# v2_0.net
KiCad netlist of a schematic drawn in Altium Designer
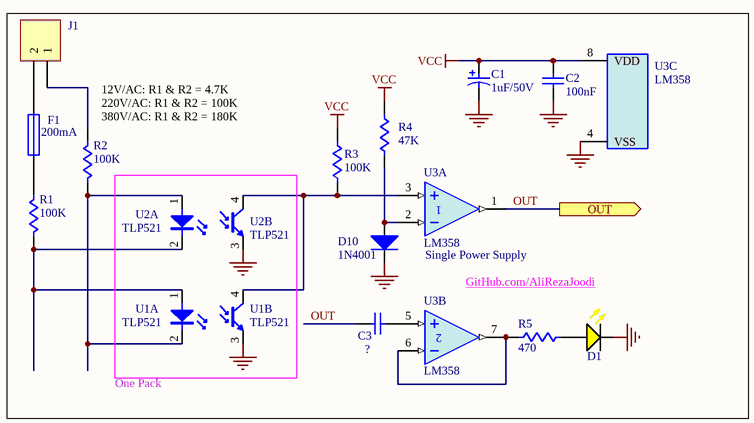
[diagram p0: v2.0.SchDoc]

(export (version "E")
  (design (tool "Eeschema 10.0.6"))
  (components
    (comp (ref "C1")
      (value "1uF/50V")
      (footprint "C_THD_EL_(P2.54-D6-H11)")
      (description "Capacitor, Electrolytic")
      (libsource (lib "Passive") (part "Capacitor_Electrolytic"))
    )
    (comp (ref "C2")
      (value "100nF")
      (footprint "C_THD_CER_(P2.54-D3.5-T1.5)")
      (description "Capacitor, Ceramic Multilayer")
      (libsource (lib "Passive") (part "Capacitor_Ceramic"))
    )
    (comp (ref "C3")
      (value "?")
      (footprint "C_THD_CER_(P2.54-D3.5-T1.5)")
      (description "Capacitor, Ceramic Multilayer")
      (libsource (lib "Passive") (part "Capacitor_Ceramic"))
    )
    (comp (ref "D1")
      (value "YELLOW")
      (footprint "LED_THD_5MM_YELLOW")
      (description "LED, Yellow")
      (fields (field (name "MANUFACTURER") "Generic Components") (field (name "PUBLISHER") "Altium Limited"))
      (libsource (lib "Display") (part "LED_YELLOW"))
    )
    (comp (ref "D10")
      (value "1N4001")
      (footprint "DIODE-0.4")
      (description "Default Diode")
      (fields (field (name "MANUFACTURER") "Generic Components") (field (name "PUBLISHER") "Altium Limited"))
      (libsource (lib "Miscellaneous Devices") (part "Diode"))
    )
    (comp (ref "F1")
      (value "200mA")
      (footprint "PIN-W2/E2.8")
      (description "Fuse")
      (fields (field (name "PUBLISHER") "Altium Limited"))
      (libsource (lib "Miscellaneous Devices") (part "Fuse 1"))
    )
    (comp (ref "J1")
      (value "Header 2")
      (footprint "Fonics_2PIN_1")
      (description "Header, 2-Pin")
      (fields (field (name "PUBLISHER") "Altium Limited"))
      (libsource (lib "Miscellaneous Connectors") (part "Header 2"))
    )
    (comp (ref "R1")
      (value "100K")
      (footprint "AXIAL-0.4")
      (description "Resistor")
      (fields
        (field (name "MANUFACTURER") "Generic Components")
        (field (name "Comment") "Res1")
        (field (name "PUBLISHER") "Altium Limited")
      )
      (libsource (lib "Miscellaneous Devices") (part "Res1"))
    )
    (comp (ref "R2")
      (value "100K")
      (footprint "AXIAL-0.4")
      (description "Resistor")
      (fields
        (field (name "MANUFACTURER") "Generic Components")
        (field (name "Comment") "Res1")
        (field (name "PUBLISHER") "Altium Limited")
      )
      (libsource (lib "Miscellaneous Devices") (part "Res1"))
    )
    (comp (ref "R3")
      (value "100K")
      (footprint "AXIAL-0.4")
      (description "Resistor")
      (fields
        (field (name "MANUFACTURER") "Generic Components")
        (field (name "Comment") "Res1")
        (field (name "PUBLISHER") "Altium Limited")
      )
      (libsource (lib "Miscellaneous Devices") (part "Res1"))
    )
    (comp (ref "R4")
      (value "47K")
      (footprint "AXIAL-0.4")
      (description "Resistor")
      (fields
        (field (name "MANUFACTURER") "Generic Components")
        (field (name "Comment") "Res1")
        (field (name "PUBLISHER") "Altium Limited")
      )
      (libsource (lib "Miscellaneous Devices") (part "Res1"))
    )
    (comp (ref "R5")
      (value "470")
      (footprint "AXIAL-0.4")
      (description "Resistor")
      (fields
        (field (name "MANUFACTURER") "Generic Components")
        (field (name "Comment") "Res1")
        (field (name "PUBLISHER") "Altium Limited")
      )
      (libsource (lib "Miscellaneous Devices") (part "Res1"))
    )
    (comp (ref "U1")
      (value "TLP521")
      (footprint "DIP-4")
      (fields (field (name "Comment") "Optoisolator") (field (name "PUBLISHER") "Altium Limited"))
      (libsource (lib "my Libraries") (part "Optoisolator"))
    )
    (comp (ref "U2")
      (value "TLP521")
      (footprint "DIP-4")
      (fields (field (name "Comment") "Optoisolator") (field (name "PUBLISHER") "Altium Limited"))
      (libsource (lib "my Libraries") (part "Optoisolator"))
    )
    (comp (ref "U3")
      (value "LM358")
      (footprint "DIP_8")
      (description "Dual Low-Power Operational Amplifier")
      (fields (field (name "PUBLISHER") "Altium Limited"))
      (libsource (lib "Op-Amp") (part "LM358"))
    )
  )
  (nets
    (net (code "1") (name "/OUT") (class "Default")
      (node (ref "C3") (pin "1") (pinfunction "1_1") (pintype "passive"))
      (node (ref "U3") (pin "1") (pinfunction "OUT_1") (pintype "output"))
    )
    (net (code "2") (name "GND") (class "Default")
      (node (ref "C1") (pin "2") (pinfunction "2_2") (pintype "passive"))
      (node (ref "C2") (pin "2") (pinfunction "2_2") (pintype "passive"))
      (node (ref "D1") (pin "2") (pinfunction "K_2") (pintype "passive"))
      (node (ref "D10") (pin "2") (pinfunction "K_2") (pintype "passive"))
      (node (ref "U1") (pin "3") (pinfunction "E_3") (pintype "passive"))
      (node (ref "U2") (pin "3") (pinfunction "E_3") (pintype "passive"))
      (node (ref "U3") (pin "4") (pinfunction "VSS_4") (pintype "power_in"))
    )
    (net (code "3") (name "Net-(D1-A)") (class "Default")
      (node (ref "D1") (pin "1") (pinfunction "A_1") (pintype "passive"))
      (node (ref "R5") (pin "2") (pinfunction "2_2") (pintype "passive"))
    )
    (net (code "4") (name "Net-(D10-A)") (class "Default")
      (node (ref "D10") (pin "1") (pinfunction "A_1") (pintype "passive"))
      (node (ref "R4") (pin "2") (pinfunction "2_2") (pintype "passive"))
      (node (ref "U3") (pin "2") (pinfunction "IN-_2") (pintype "input"))
    )
    (net (code "5") (name "Net-(F1-Pad1)") (class "Default")
      (node (ref "F1") (pin "1") (pinfunction "1_1") (pintype "passive"))
      (node (ref "R1") (pin "1") (pinfunction "1_1") (pintype "passive"))
    )
    (net (code "6") (name "Net-(F1-Pad2)") (class "Default")
      (node (ref "F1") (pin "2") (pinfunction "2_2") (pintype "passive"))
      (node (ref "J1") (pin "2") (pinfunction "2_2") (pintype "passive"))
    )
    (net (code "7") (name "Net-(J1-Pad1)") (class "Default")
      (node (ref "J1") (pin "1") (pinfunction "1_1") (pintype "passive"))
      (node (ref "R2") (pin "1") (pinfunction "1_1") (pintype "passive"))
    )
    (net (code "8") (name "Net-(U1A-A)") (class "Default")
      (node (ref "R1") (pin "2") (pinfunction "2_2") (pintype "passive"))
      (node (ref "U1") (pin "1") (pinfunction "A_1") (pintype "power_in"))
      (node (ref "U2") (pin "2") (pinfunction "K_2") (pintype "power_in"))
    )
    (net (code "9") (name "Net-(U1A-K)") (class "Default")
      (node (ref "R2") (pin "2") (pinfunction "2_2") (pintype "passive"))
      (node (ref "U1") (pin "2") (pinfunction "K_2") (pintype "power_in"))
      (node (ref "U2") (pin "1") (pinfunction "A_1") (pintype "power_in"))
    )
    (net (code "10") (name "Net-(U1B-C)") (class "Default")
      (node (ref "R3") (pin "2") (pinfunction "2_2") (pintype "passive"))
      (node (ref "U1") (pin "4") (pinfunction "C_4") (pintype "passive"))
      (node (ref "U2") (pin "4") (pinfunction "C_4") (pintype "passive"))
      (node (ref "U3") (pin "3") (pinfunction "IN+_3") (pintype "input"))
    )
    (net (code "11") (name "Net-(U3B-IN+)") (class "Default")
      (node (ref "C3") (pin "2") (pinfunction "2_2") (pintype "passive"))
      (node (ref "U3") (pin "5") (pinfunction "IN+_5") (pintype "input"))
    )
    (net (code "12") (name "Net-(U3B-IN-)") (class "Default")
      (node (ref "R5") (pin "1") (pinfunction "1_1") (pintype "passive"))
      (node (ref "U3") (pin "6") (pinfunction "IN-_6") (pintype "input"))
      (node (ref "U3") (pin "7") (pinfunction "OUT_7") (pintype "output"))
    )
    (net (code "13") (name "VCC") (class "Default")
      (node (ref "C1") (pin "1") (pinfunction "1_1") (pintype "passive"))
      (node (ref "C2") (pin "1") (pinfunction "1_1") (pintype "passive"))
      (node (ref "R3") (pin "1") (pinfunction "1_1") (pintype "passive"))
      (node (ref "R4") (pin "1") (pinfunction "1_1") (pintype "passive"))
      (node (ref "U3") (pin "8") (pinfunction "VDD_8") (pintype "passive"))
    )
  )
)
